# Power_Supply.net
KiCad netlist of a schematic drawn in Altium Designer
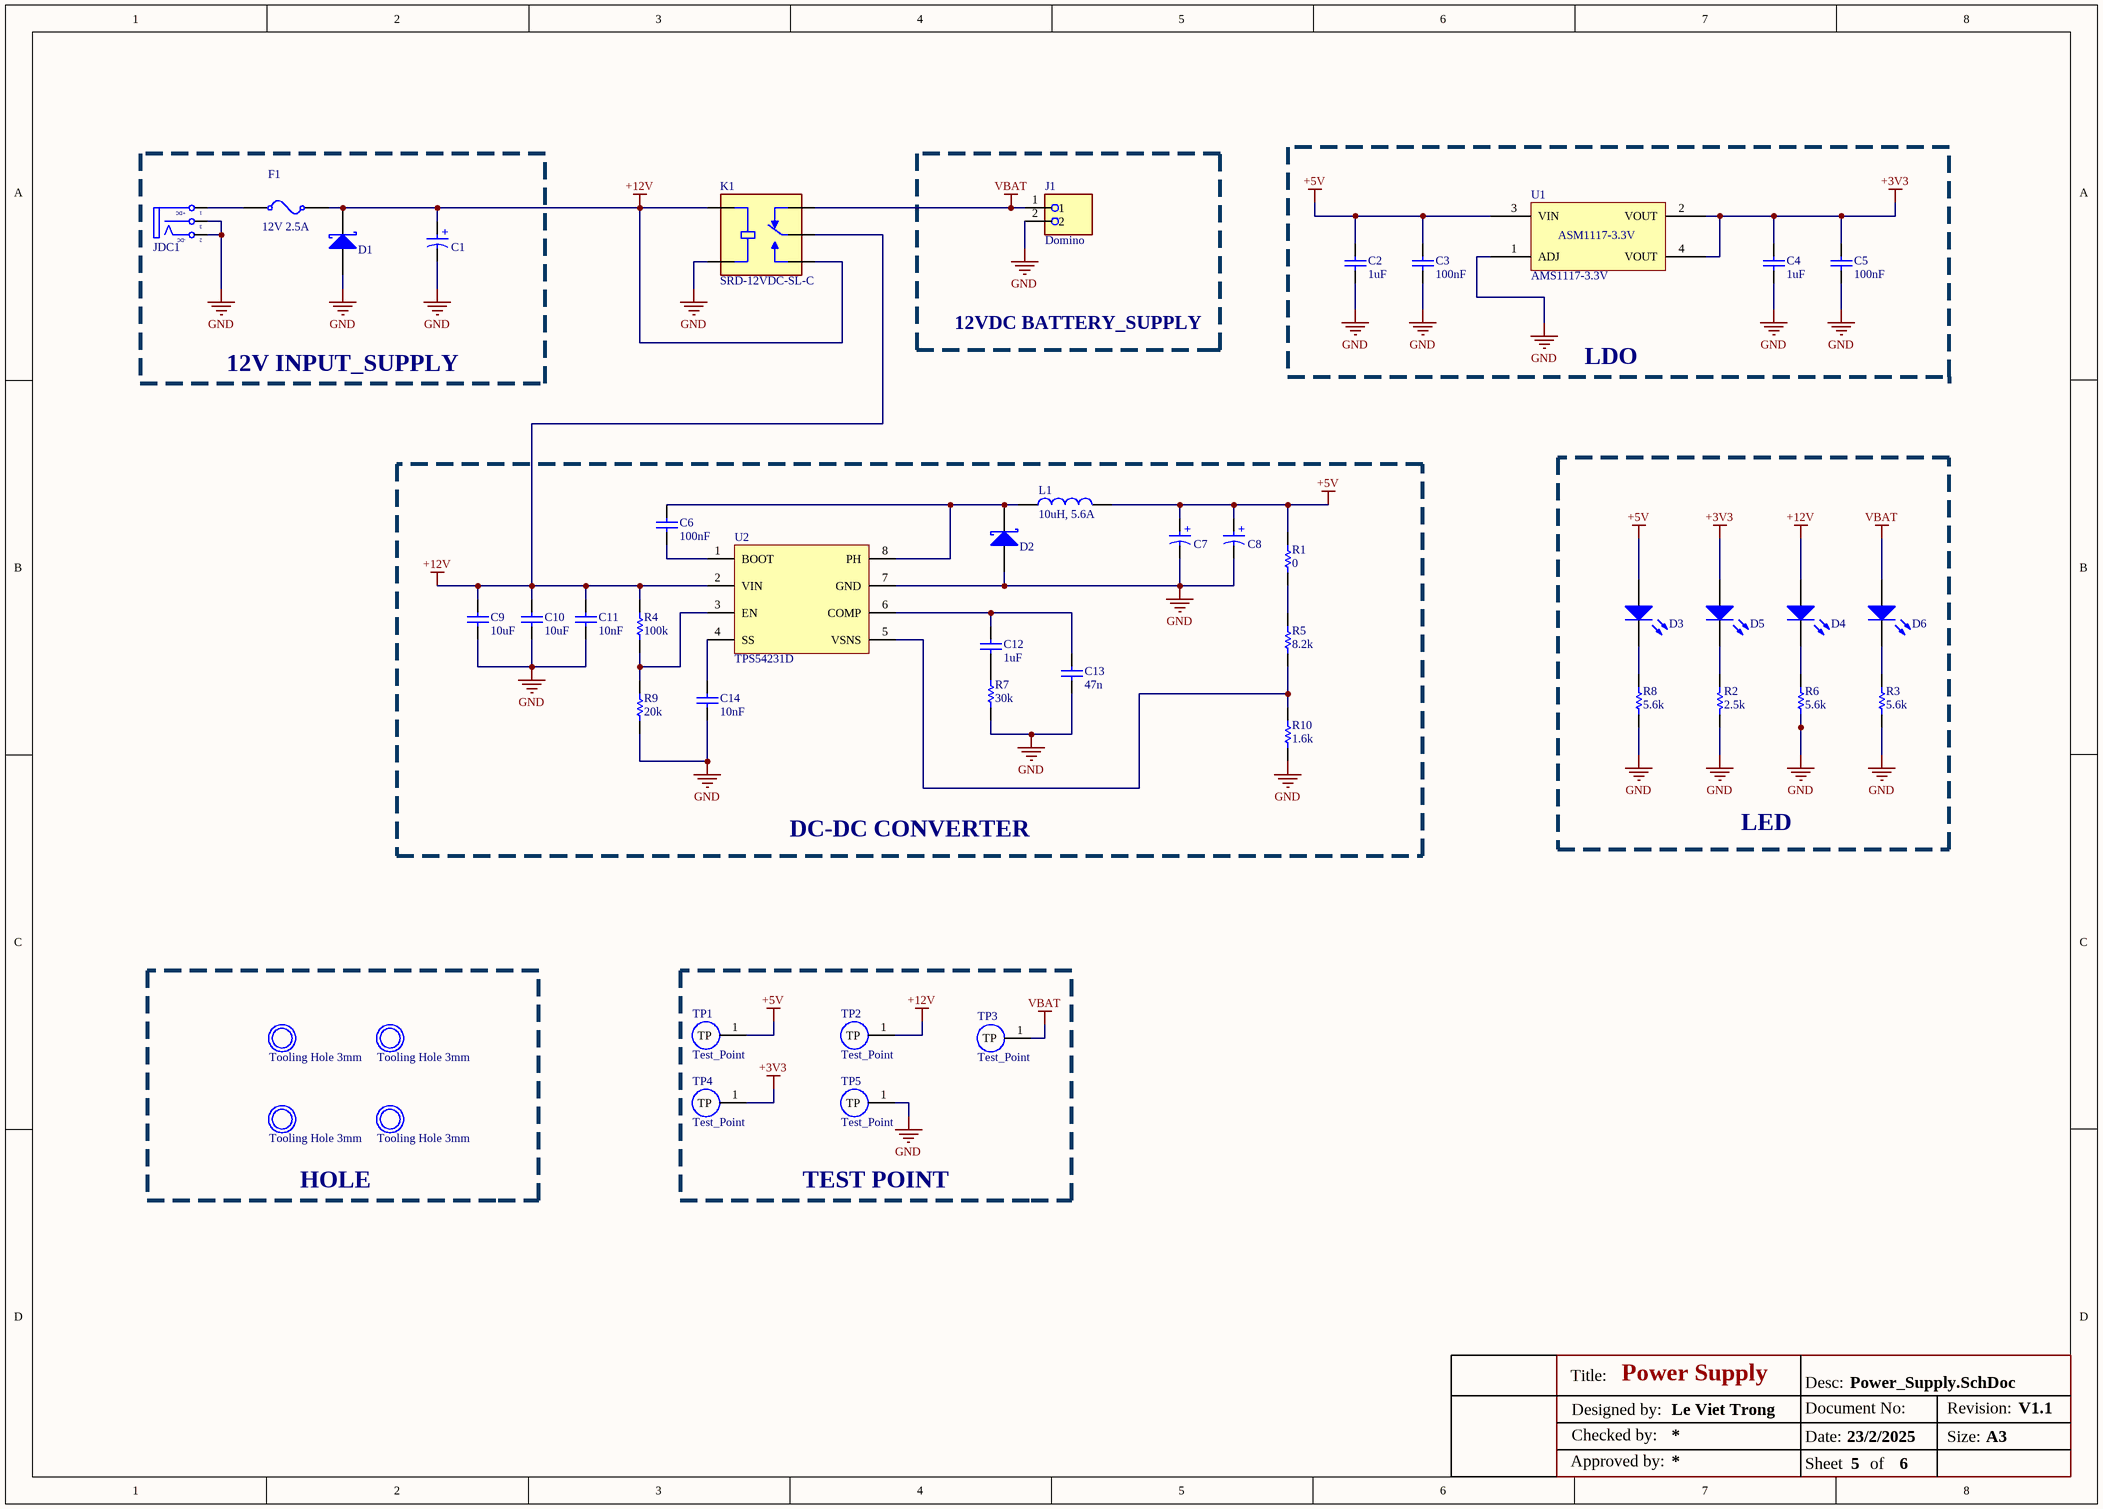
[diagram p0: Power_Supply.SchDoc]

(export (version "E")
  (design (tool "Eeschema 10.0.6"))
  (components
    (comp (ref "C1")
      (value "47uF")
      (footprint "WCAP-ASLI_D4H5.5")
      (description "V-Chip, D4 x H5.5mm, 22uF, 16V")
      (libsource (lib "SMIOT_Lib_Schematic") (part "865080340003"))
    )
    (comp (ref "C2")
      (value "1uF")
      (footprint "CAP_0603")
      (description "CAP, size 0603, 1uF")
      (libsource (lib "SMIOT_Lib_Schematic") (part "01060310510"))
    )
    (comp (ref "C3")
      (value "100nF")
      (footprint "CAP_0603")
      (description "CAP, size 0603, 100nF")
      (libsource (lib "SMIOT_Lib_Schematic") (part "01060310410"))
    )
    (comp (ref "C4")
      (value "1uF")
      (footprint "CAP_0603")
      (description "CAP, size 0603, 1uF")
      (libsource (lib "SMIOT_Lib_Schematic") (part "01060310510"))
    )
    (comp (ref "C5")
      (value "100nF")
      (footprint "CAP_0603")
      (description "CAP, size 0603, 100nF")
      (libsource (lib "SMIOT_Lib_Schematic") (part "01060310410"))
    )
    (comp (ref "C6")
      (value "100nF")
      (footprint "CAP_0603")
      (description "CAP, size 0603, 100nF")
      (libsource (lib "SMIOT_Lib_Schematic") (part "01060310410"))
    )
    (comp (ref "C7")
      (value "47uF")
      (footprint "WCAP-ASLI_D5H5.5")
      (description "V-Chip, D5 x H5.5mm, 47uF, 16V")
      (libsource (lib "SMIOT_Lib_Schematic") (part "865080342006"))
    )
    (comp (ref "C8")
      (value "47uF")
      (footprint "WCAP-ASLI_D5H5.5")
      (description "V-Chip, D5 x H5.5mm, 47uF, 16V")
      (libsource (lib "SMIOT_Lib_Schematic") (part "865080342006"))
    )
    (comp (ref "C9")
      (value "10uF")
      (footprint "CAP_0603")
      (description "CAP, size 0603,10uF")
      (libsource (lib "SMIOT_Lib_Schematic") (part "01060310010"))
    )
    (comp (ref "C10")
      (value "10uF")
      (footprint "CAP_0603")
      (description "CAP, size 0603,10uF")
      (libsource (lib "SMIOT_Lib_Schematic") (part "01060310010"))
    )
    (comp (ref "C11")
      (value "10nF")
      (footprint "CAP_0603")
      (description "CAP, size 0603, 10nF")
      (libsource (lib "SMIOT_Lib_Schematic") (part "01060310310"))
    )
    (comp (ref "C12")
      (value "1uF")
      (footprint "CAP_0603")
      (description "CAP, size 0603, 1uF")
      (libsource (lib "SMIOT_Lib_Schematic") (part "01060310510"))
    )
    (comp (ref "C13")
      (value "47n")
      (footprint "CAP_0603")
      (description "CAP, size 0603, 47nF")
      (libsource (lib "SMIOT_Lib_Schematic") (part "01060347310"))
    )
    (comp (ref "C14")
      (value "10nF")
      (footprint "CAP_0603")
      (description "CAP, size 0603, 10nF")
      (libsource (lib "SMIOT_Lib_Schematic") (part "01060310310"))
    )
    (comp (ref "D1")
      (value "D Schottky")
      (footprint "SS34")
      (description "Schottky Diode")
      (fields (field (name "PUBLISHER") "Altium Limited"))
      (libsource (lib "Board_C24") (part "D Schottky"))
    )
    (comp (ref "D2")
      (value "D Schottky")
      (footprint "SS34")
      (description "Schottky Diode")
      (fields (field (name "PUBLISHER") "Altium Limited"))
      (libsource (lib "SMIOT_Lib_Schematic") (part "D Schottky"))
    )
    (comp (ref "D3")
      (value "LED SMD")
      (footprint "LED_0805_Blue")
      (description "LED")
      (libsource (lib "SMIOT_Lib_Schematic") (part "LED SMD"))
    )
    (comp (ref "D4")
      (value "LED SMD")
      (footprint "LED_0805_Blue")
      (description "LED")
      (libsource (lib "SMIOT_Lib_Schematic") (part "LED SMD"))
    )
    (comp (ref "D5")
      (value "LED SMD")
      (footprint "LED_0805_Blue")
      (description "LED")
      (libsource (lib "SMIOT_Lib_Schematic") (part "LED SMD"))
    )
    (comp (ref "D6")
      (value "LED SMD")
      (footprint "LED_0805_Blue")
      (description "LED")
      (libsource (lib "SMIOT_Lib_Schematic") (part "LED SMD"))
    )
    (comp (ref "F1")
      (value "12V 2.5A")
      (footprint "Fuse_SMD_1812")
      (description "Resettable Fuse, Size 1812, 8V, 2A")
      (fields (field (name "MANUFACTURER") "Littelfuse"))
      (libsource (lib "SMIOT_Lib_Schematic") (part "061812200008"))
    )
    (comp (ref "H1")
      (value "Tooling Hole 3mm")
      (footprint "2mm")
      (description "Tooling Hole 1mm")
      (libsource (lib "SMIOT_Lib_Schematic") (part "Tooling Hole 2mm"))
    )
    (comp (ref "H2")
      (value "Tooling Hole 3mm")
      (footprint "2mm")
      (description "Tooling Hole 1mm")
      (libsource (lib "SMIOT_Lib_Schematic") (part "Tooling Hole 2mm"))
    )
    (comp (ref "H3")
      (value "Tooling Hole 3mm")
      (footprint "2mm")
      (description "Tooling Hole 1mm")
      (libsource (lib "SMIOT_Lib_Schematic") (part "Tooling Hole 2mm"))
    )
    (comp (ref "H4")
      (value "Tooling Hole 3mm")
      (footprint "2mm")
      (description "Tooling Hole 1mm")
      (libsource (lib "SMIOT_Lib_Schematic") (part "Tooling Hole 2mm"))
    )
    (comp (ref "J1")
      (value "Domino")
      (footprint "PHOENIX_1935161")
      (description "PCB Terminal Screw 5mm 16AWG 400V 17.5A 2 Position COMBICON PT Series ¦ Phoenix Contact 1935161")
      (fields (field (name "MF") "Phoenix Contact") (field (name "MP") "1935161"))
      (libsource (lib "Domino") (part "Domino"))
    )
    (comp (ref "JDC1")
      (value "Jack DC")
      (footprint "DC-IN")
      (description "Jack DC input")
      (libsource (lib "SMIOT_Lib_Schematic") (part "Jack DC"))
    )
    (comp (ref "K1")
      (value "SRD-12VDC-SL-C")
      (footprint "RELAY_SRD-12VDC-SL-C")
      (description "General Purpose Non Latching 12VDC SPDT Through Hole Relays RoHS")
      (fields (field (name "MF") "Songle Relay"))
      (libsource (lib "RELAY") (part "SRD-12VDC-SL-C"))
    )
    (comp (ref "L1")
      (value "10uH, 5.6A")
      (footprint "WE-PD2A_5848")
      (description "WE-PD2A SMT Power Inductor, size 5848, 10uH, 2.2A")
      (fields
        (field (name "MANUFACTURER PART NUMBER") "78477410")
        (field (name "MANUFACTURER") "Wurth Elektronik")
      )
      (libsource (lib "SMIOT_Lib_Schematic") (part "78477410"))
    )
    (comp (ref "R1")
      (value "0")
      (footprint "resistor_0603")
      (description "RES, 0 Ohm, size 0603, 1%")
      (libsource (lib "SMIOT_Lib_Schematic") (part "0006030001"))
    )
    (comp (ref "R2")
      (value "2.5k")
      (footprint "resistor_0603")
      (description "RES, 2.5K Ohm, size 0603, 5%")
      (libsource (lib "SMIOT_Lib_Schematic") (part "0006032525"))
    )
    (comp (ref "R3")
      (value "5.6k")
      (footprint "resistor_0603")
      (description "RES, 5.6k Ohm, size 0603, 1%")
      (libsource (lib "SMIOT_Lib_Schematic") (part "0006035621"))
    )
    (comp (ref "R4")
      (value "100k")
      (footprint "resistor_0603")
      (description "RES, 100k Ohm, size 0603, 1%")
      (libsource (lib "SMIOT_Lib_Schematic") (part "0006031041"))
    )
    (comp (ref "R5")
      (value "8.2k")
      (footprint "resistor_0603")
      (description "RES, 8.2 kOhms, size 0603, 1%")
      (libsource (lib "SMIOT_Lib_Schematic") (part "0006038251"))
    )
    (comp (ref "R6")
      (value "5.6k")
      (footprint "resistor_0603")
      (description "RES, 5.6k Ohm, size 0603, 1%")
      (libsource (lib "SMIOT_Lib_Schematic") (part "0006035621"))
    )
    (comp (ref "R7")
      (value "30k")
      (footprint "resistor_0603")
      (description "RES, 30k Ohm, size 0603, 1%")
      (libsource (lib "SMIOT_Lib_Schematic") (part "0006033205"))
    )
    (comp (ref "R8")
      (value "5.6k")
      (footprint "resistor_0603")
      (description "RES, 5.6k Ohm, size 0603, 1%")
      (libsource (lib "SMIOT_Lib_Schematic") (part "0006035621"))
    )
    (comp (ref "R9")
      (value "20k")
      (footprint "resistor_0603")
      (description "RES, 20 kOhms, size 0603, 1%")
      (libsource (lib "SMIOT_Lib_Schematic") (part "0006032031"))
    )
    (comp (ref "R10")
      (value "1.6k")
      (footprint "resistor_0603")
      (description "RES, 1.5 kOhms, size 0603, 1%")
      (libsource (lib "SMIOT_Lib_Schematic") (part "0006031521"))
    )
    (comp (ref "TP1")
      (value "Test_Point")
      (footprint "TP_2MM")
      (description "Test point, 2mm radius")
      (libsource (lib "SMIOT_Lib_Schematic") (part "Test_Point"))
    )
    (comp (ref "TP2")
      (value "Test_Point")
      (footprint "TP_2MM")
      (description "Test point, 2mm radius")
      (libsource (lib "SMIOT_Lib_Schematic") (part "Test_Point"))
    )
    (comp (ref "TP3")
      (value "Test_Point")
      (footprint "TP_2MM")
      (description "Test point, 2mm radius")
      (libsource (lib "SMIOT_Lib_Schematic") (part "Test_Point"))
    )
    (comp (ref "TP4")
      (value "Test_Point")
      (footprint "TP_2MM")
      (description "Test point, 2mm radius")
      (libsource (lib "SMIOT_Lib_Schematic") (part "Test_Point"))
    )
    (comp (ref "TP5")
      (value "Test_Point")
      (footprint "TP_2MM")
      (description "Test point, 2mm radius")
      (libsource (lib "SMIOT_Lib_Schematic") (part "Test_Point"))
    )
    (comp (ref "U1")
      (value "AMS1117-3.3V")
      (footprint "AMS1117-3.3V SOT223")
      (description "AMS1117-3.3V, OUT 3.3V 1A.")
      (fields (field (name "MANUFACTURER") "AMS"))
      (libsource (lib "SMIOT_Lib_Schematic") (part "AMS1117-3.3V"))
    )
    (comp (ref "U2")
      (value "TPS54231D")
      (footprint "SOIC8")
      (description "Buck Switching Regulator IC Positive Adjustable 0.8V 1 Output 2A 8-SOIC (0.154\", 3.90mm Width)")
      (fields (field (name "MFR") "Texas Instruments"))
      (libsource (lib "SMIOT_Lib_Schematic") (part "TPS54231"))
    )
  )
  (nets
    (net (code "1") (name "+3V3") (class "Default")
      (node (ref "C4") (pin "2") (pinfunction "2_2") (pintype "passive"))
      (node (ref "C5") (pin "2") (pinfunction "2_2") (pintype "passive"))
      (node (ref "D5") (pin "1") (pinfunction "A_1") (pintype "passive"))
      (node (ref "TP4") (pin "1") (pinfunction "TP_1") (pintype "passive"))
      (node (ref "U1") (pin "2") (pinfunction "VOUT_2") (pintype "passive"))
      (node (ref "U1") (pin "4") (pinfunction "VOUT_4") (pintype "power_in"))
    )
    (net (code "2") (name "+5V") (class "Default")
      (node (ref "C2") (pin "2") (pinfunction "2_2") (pintype "passive"))
      (node (ref "C3") (pin "2") (pinfunction "2_2") (pintype "passive"))
      (node (ref "C7") (pin "1") (pinfunction "P_1") (pintype "passive"))
      (node (ref "C8") (pin "1") (pinfunction "P_1") (pintype "passive"))
      (node (ref "D3") (pin "1") (pinfunction "A_1") (pintype "passive"))
      (node (ref "L1") (pin "2") (pinfunction "2_2") (pintype "passive"))
      (node (ref "R1") (pin "2") (pinfunction "2_2") (pintype "passive"))
      (node (ref "TP1") (pin "1") (pinfunction "TP_1") (pintype "passive"))
      (node (ref "U1") (pin "3") (pinfunction "VIN_3") (pintype "passive"))
    )
    (net (code "3") (name "+12V") (class "Default")
      (node (ref "C1") (pin "1") (pinfunction "P_1") (pintype "passive"))
      (node (ref "C10") (pin "2") (pinfunction "2_2") (pintype "passive"))
      (node (ref "C11") (pin "2") (pinfunction "2_2") (pintype "passive"))
      (node (ref "C9") (pin "2") (pinfunction "2_2") (pintype "passive"))
      (node (ref "D1") (pin "2") (pinfunction "K_2") (pintype "passive"))
      (node (ref "D4") (pin "1") (pinfunction "A_1") (pintype "passive"))
      (node (ref "F1") (pin "1") (pinfunction "1_1") (pintype "passive"))
      (node (ref "K1") (pin "COIL1") (pinfunction "COIL1_COIL1") (pintype "passive"))
      (node (ref "K1") (pin "COM") (pinfunction "COM_COM") (pintype "passive"))
      (node (ref "K1") (pin "NO") (pinfunction "NO_NO") (pintype "passive"))
      (node (ref "R4") (pin "2") (pinfunction "2_2") (pintype "passive"))
      (node (ref "TP2") (pin "1") (pinfunction "TP_1") (pintype "passive"))
      (node (ref "U2") (pin "2") (pinfunction "VIN_2") (pintype "passive"))
    )
    (net (code "4") (name "GND") (class "Default")
      (node (ref "C1") (pin "2") (pinfunction "N_2") (pintype "passive"))
      (node (ref "C10") (pin "1") (pinfunction "1_1") (pintype "passive"))
      (node (ref "C11") (pin "1") (pinfunction "1_1") (pintype "passive"))
      (node (ref "C13") (pin "1") (pinfunction "1_1") (pintype "passive"))
      (node (ref "C14") (pin "1") (pinfunction "1_1") (pintype "passive"))
      (node (ref "C2") (pin "1") (pinfunction "1_1") (pintype "passive"))
      (node (ref "C3") (pin "1") (pinfunction "1_1") (pintype "passive"))
      (node (ref "C4") (pin "1") (pinfunction "1_1") (pintype "passive"))
      (node (ref "C5") (pin "1") (pinfunction "1_1") (pintype "passive"))
      (node (ref "C7") (pin "2") (pinfunction "N_2") (pintype "passive"))
      (node (ref "C8") (pin "2") (pinfunction "N_2") (pintype "passive"))
      (node (ref "C9") (pin "1") (pinfunction "1_1") (pintype "passive"))
      (node (ref "D1") (pin "1") (pinfunction "A_1") (pintype "passive"))
      (node (ref "D2") (pin "1") (pinfunction "A_1") (pintype "passive"))
      (node (ref "J1") (pin "2") (pinfunction "2_2") (pintype "passive"))
      (node (ref "JDC1") (pin "2") (pinfunction "TN_2") (pintype "passive"))
      (node (ref "JDC1") (pin "3") (pinfunction "S_3") (pintype "power_in"))
      (node (ref "K1") (pin "COIL2") (pinfunction "COIL2_COIL2") (pintype "passive"))
      (node (ref "R10") (pin "1") (pinfunction "1_1") (pintype "passive"))
      (node (ref "R2") (pin "1") (pinfunction "1_1") (pintype "passive"))
      (node (ref "R3") (pin "1") (pinfunction "1_1") (pintype "passive"))
      (node (ref "R6") (pin "1") (pinfunction "1_1") (pintype "passive"))
      (node (ref "R7") (pin "1") (pinfunction "1_1") (pintype "passive"))
      (node (ref "R8") (pin "1") (pinfunction "1_1") (pintype "passive"))
      (node (ref "R9") (pin "1") (pinfunction "1_1") (pintype "passive"))
      (node (ref "TP5") (pin "1") (pinfunction "TP_1") (pintype "passive"))
      (node (ref "U1") (pin "1") (pinfunction "ADJ_1") (pintype "power_in"))
      (node (ref "U2") (pin "7") (pinfunction "GND_7") (pintype "passive"))
    )
    (net (code "5") (name "Net-(C12-Pad2)") (class "Default")
      (node (ref "C12") (pin "2") (pinfunction "2_2") (pintype "passive"))
      (node (ref "R7") (pin "2") (pinfunction "2_2") (pintype "passive"))
    )
    (net (code "6") (name "Net-(D2-K)") (class "Default")
      (node (ref "C6") (pin "2") (pinfunction "2_2") (pintype "passive"))
      (node (ref "D2") (pin "2") (pinfunction "K_2") (pintype "passive"))
      (node (ref "L1") (pin "1") (pinfunction "1_1") (pintype "passive"))
      (node (ref "U2") (pin "8") (pinfunction "PH_8") (pintype "passive"))
    )
    (net (code "7") (name "Net-(D3-K)") (class "Default")
      (node (ref "D3") (pin "2") (pinfunction "K_2") (pintype "passive"))
      (node (ref "R8") (pin "2") (pinfunction "2_2") (pintype "passive"))
    )
    (net (code "8") (name "Net-(D4-K)") (class "Default")
      (node (ref "D4") (pin "2") (pinfunction "K_2") (pintype "passive"))
      (node (ref "R6") (pin "2") (pinfunction "2_2") (pintype "passive"))
    )
    (net (code "9") (name "Net-(D5-K)") (class "Default")
      (node (ref "D5") (pin "2") (pinfunction "K_2") (pintype "passive"))
      (node (ref "R2") (pin "2") (pinfunction "2_2") (pintype "passive"))
    )
    (net (code "10") (name "Net-(D6-K)") (class "Default")
      (node (ref "D6") (pin "2") (pinfunction "K_2") (pintype "passive"))
      (node (ref "R3") (pin "2") (pinfunction "2_2") (pintype "passive"))
    )
    (net (code "11") (name "Net-(JDC1-T)") (class "Default")
      (node (ref "F1") (pin "0") (pinfunction "0_0") (pintype "passive"))
      (node (ref "JDC1") (pin "1") (pinfunction "T_1") (pintype "passive"))
    )
    (net (code "12") (name "Net-(R1-Pad1)") (class "Default")
      (node (ref "R1") (pin "1") (pinfunction "1_1") (pintype "passive"))
      (node (ref "R5") (pin "2") (pinfunction "2_2") (pintype "passive"))
    )
    (net (code "13") (name "Net-(U2-BOOT)") (class "Default")
      (node (ref "C6") (pin "1") (pinfunction "1_1") (pintype "passive"))
      (node (ref "U2") (pin "1") (pinfunction "BOOT_1") (pintype "passive"))
    )
    (net (code "14") (name "Net-(U2-COMP)") (class "Default")
      (node (ref "C12") (pin "1") (pinfunction "1_1") (pintype "passive"))
      (node (ref "C13") (pin "2") (pinfunction "2_2") (pintype "passive"))
      (node (ref "U2") (pin "6") (pinfunction "COMP_6") (pintype "passive"))
    )
    (net (code "15") (name "Net-(U2-EN)") (class "Default")
      (node (ref "R4") (pin "1") (pinfunction "1_1") (pintype "passive"))
      (node (ref "R9") (pin "2") (pinfunction "2_2") (pintype "passive"))
      (node (ref "U2") (pin "3") (pinfunction "EN_3") (pintype "passive"))
    )
    (net (code "16") (name "Net-(U2-SS)") (class "Default")
      (node (ref "C14") (pin "2") (pinfunction "2_2") (pintype "passive"))
      (node (ref "U2") (pin "4") (pinfunction "SS_4") (pintype "passive"))
    )
    (net (code "17") (name "Net-(U2-VSNS)") (class "Default")
      (node (ref "R10") (pin "2") (pinfunction "2_2") (pintype "passive"))
      (node (ref "R5") (pin "1") (pinfunction "1_1") (pintype "passive"))
      (node (ref "U2") (pin "5") (pinfunction "VSNS_5") (pintype "passive"))
    )
    (net (code "18") (name "VBAT") (class "Default")
      (node (ref "D6") (pin "1") (pinfunction "A_1") (pintype "passive"))
      (node (ref "J1") (pin "1") (pinfunction "1_1") (pintype "passive"))
      (node (ref "K1") (pin "NC") (pinfunction "NC_NC") (pintype "passive"))
      (node (ref "TP3") (pin "1") (pinfunction "TP_1") (pintype "passive"))
    )
  )
)
